# LZ3003_3.net
KiCad netlist of a schematic drawn in EAGLE
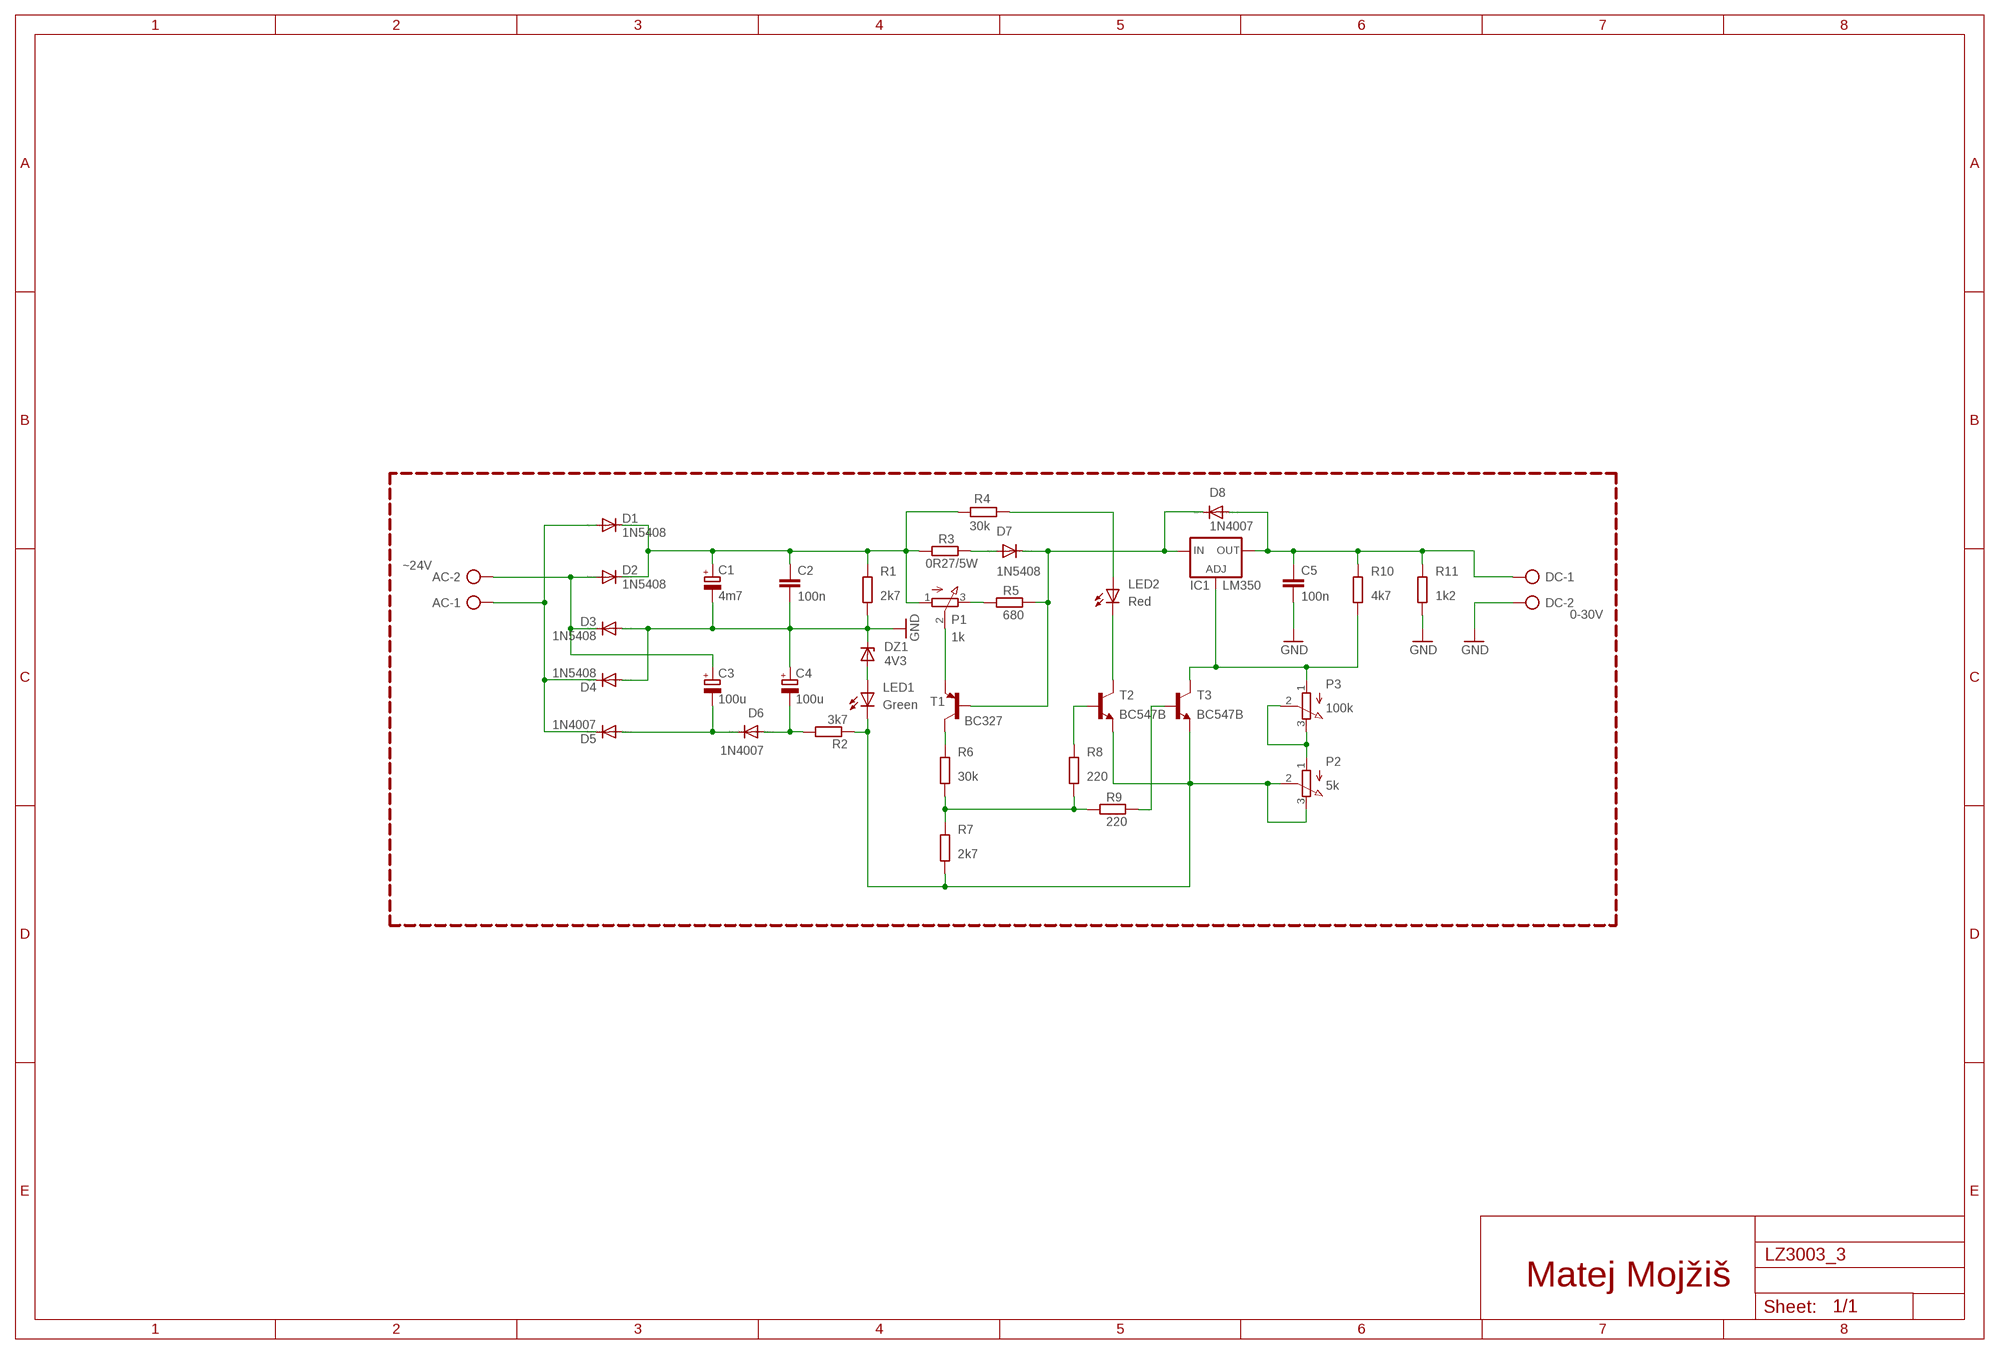
[diagram p0: schematic, sheet 1]

(export (version "E")
  (design (tool "Eeschema 10.0.6"))
  (components
    (comp (ref "AC")
      (value "~24V")
      (footprint "eagle-import:W237-102")
      (fields (field (name "MPN") "237-102"))
      (libsource (lib "eagle-import") (part "W237-102"))
    )
    (comp (ref "C1")
      (value "4m7")
      (footprint "eagle-import:E7,5-16")
      (libsource (lib "eagle-import") (part "CPOL-EUE7.5-16"))
    )
    (comp (ref "C2")
      (value "100n")
      (footprint "eagle-import:C050-025X075")
      (libsource (lib "eagle-import") (part "C-EU050-025X075"))
    )
    (comp (ref "C3")
      (value "100u")
      (footprint "eagle-import:E5-8,5")
      (libsource (lib "eagle-import") (part "CPOL-EUE5-8.5"))
    )
    (comp (ref "C4")
      (value "100u")
      (footprint "eagle-import:E5-8,5")
      (libsource (lib "eagle-import") (part "CPOL-EUE5-8.5"))
    )
    (comp (ref "C5")
      (value "100n")
      (footprint "eagle-import:C050-025X075")
      (libsource (lib "eagle-import") (part "C-EU050-025X075"))
    )
    (comp (ref "D1")
      (value "1N5408")
      (footprint "eagle-import:DO201-15")
      (libsource (lib "eagle-import") (part "1N5400"))
    )
    (comp (ref "D2")
      (value "1N5408")
      (footprint "eagle-import:DO201-15")
      (libsource (lib "eagle-import") (part "1N5400"))
    )
    (comp (ref "D3")
      (value "1N5408")
      (footprint "eagle-import:DO201-15")
      (libsource (lib "eagle-import") (part "1N5400"))
    )
    (comp (ref "D4")
      (value "1N5408")
      (footprint "eagle-import:DO201-15")
      (libsource (lib "eagle-import") (part "1N5400"))
    )
    (comp (ref "D5")
      (value "1N4007")
      (footprint "eagle-import:DO41-10")
      (libsource (lib "eagle-import") (part "1N4004"))
    )
    (comp (ref "D6")
      (value "1N4007")
      (footprint "eagle-import:DO41-10")
      (libsource (lib "eagle-import") (part "1N4004"))
    )
    (comp (ref "D7")
      (value "1N5408")
      (footprint "eagle-import:DO201-15")
      (libsource (lib "eagle-import") (part "1N5400"))
    )
    (comp (ref "D8")
      (value "1N4007")
      (footprint "eagle-import:DO41-10")
      (libsource (lib "eagle-import") (part "1N4004"))
    )
    (comp (ref "DC")
      (value "0-30V")
      (footprint "eagle-import:W237-102")
      (fields (field (name "MPN") "237-102"))
      (libsource (lib "eagle-import") (part "W237-102"))
    )
    (comp (ref "DZ1")
      (value "4V3")
      (footprint "eagle-import:DO34Z7")
      (libsource (lib "eagle-import") (part "ZENER-DIODEDO34-7"))
    )
    (comp (ref "IC1")
      (value "LM350")
      (footprint "eagle-import:317TS")
      (libsource (lib "eagle-import") (part "LM317TS"))
    )
    (comp (ref "LED1")
      (value "Green")
      (footprint "eagle-import:LED5MM")
      (libsource (lib "eagle-import") (part "LED5MM"))
    )
    (comp (ref "LED2")
      (value "Red")
      (footprint "eagle-import:LED5MM")
      (libsource (lib "eagle-import") (part "LED5MM"))
    )
    (comp (ref "P1")
      (value "1k")
      (footprint "eagle-import:3RP_1610N")
      (libsource (lib "eagle-import") (part "3RP/1610N"))
    )
    (comp (ref "P2")
      (value "5k")
      (footprint "eagle-import:3RP_1610N")
      (libsource (lib "eagle-import") (part "3RP/1610N"))
    )
    (comp (ref "P3")
      (value "100k")
      (footprint "eagle-import:3RP_1610N")
      (libsource (lib "eagle-import") (part "3RP/1610N"))
    )
    (comp (ref "R1")
      (value "2k7")
      (footprint "eagle-import:0207_7")
      (libsource (lib "eagle-import") (part "R-EU_0207/7"))
    )
    (comp (ref "R2")
      (value "3k7")
      (footprint "eagle-import:0207_7")
      (libsource (lib "eagle-import") (part "R-EU_0207/7"))
    )
    (comp (ref "R3")
      (value "0R27/5W")
      (footprint "eagle-import:0617_22")
      (libsource (lib "eagle-import") (part "R-EU_0617/22"))
    )
    (comp (ref "R4")
      (value "30k")
      (footprint "eagle-import:0207_7")
      (libsource (lib "eagle-import") (part "R-EU_0207/7"))
    )
    (comp (ref "R5")
      (value "680")
      (footprint "eagle-import:0207_7")
      (libsource (lib "eagle-import") (part "R-EU_0207/7"))
    )
    (comp (ref "R6")
      (value "30k")
      (footprint "eagle-import:0207_7")
      (libsource (lib "eagle-import") (part "R-EU_0207/7"))
    )
    (comp (ref "R7")
      (value "2k7")
      (footprint "eagle-import:0207_7")
      (libsource (lib "eagle-import") (part "R-EU_0207/7"))
    )
    (comp (ref "R8")
      (value "220")
      (footprint "eagle-import:0207_7")
      (libsource (lib "eagle-import") (part "R-EU_0207/7"))
    )
    (comp (ref "R9")
      (value "220")
      (footprint "eagle-import:0207_7")
      (libsource (lib "eagle-import") (part "R-EU_0207/7"))
    )
    (comp (ref "R10")
      (value "4k7")
      (footprint "eagle-import:0207_7")
      (libsource (lib "eagle-import") (part "R-EU_0207/7"))
    )
    (comp (ref "R11")
      (value "1k2")
      (footprint "eagle-import:0207_7")
      (libsource (lib "eagle-import") (part "R-EU_0207/7"))
    )
    (comp (ref "T1")
      (value "BC327")
      (footprint "eagle-import:TO92-EBC")
      (libsource (lib "eagle-import") (part "BC327"))
    )
    (comp (ref "T2")
      (value "BC547B")
      (footprint "eagle-import:TO92-CBE")
      (libsource (lib "eagle-import") (part "-NPN-TO92-CBEBC547B"))
    )
    (comp (ref "T3")
      (value "BC547B")
      (footprint "eagle-import:TO92-CBE")
      (libsource (lib "eagle-import") (part "-NPN-TO92-CBEBC547B"))
    )
  )
  (nets
    (net (code "1") (name "GND") (class "Default")
      (node (ref "C1") (pin "-") (pinfunction "-_-") (pintype "passive"))
      (node (ref "C2") (pin "2") (pinfunction "2_2") (pintype "passive"))
      (node (ref "C4") (pin "+") (pinfunction "+_+") (pintype "passive"))
      (node (ref "C5") (pin "2") (pinfunction "2_2") (pintype "passive"))
      (node (ref "D3") (pin "A") (pinfunction "A_A") (pintype "passive"))
      (node (ref "D4") (pin "A") (pinfunction "A_A") (pintype "passive"))
      (node (ref "DC") (pin "2") (pinfunction "KL_2") (pintype "passive"))
      (node (ref "DZ1") (pin "C") (pinfunction "C_C") (pintype "passive"))
      (node (ref "R1") (pin "2") (pinfunction "2_2") (pintype "passive"))
      (node (ref "R11") (pin "1") (pinfunction "1_1") (pintype "passive"))
    )
    (net (code "2") (name "Net-(ACA-KL)") (class "Default")
      (node (ref "AC") (pin "1") (pinfunction "KL_1") (pintype "passive"))
      (node (ref "D1") (pin "A") (pinfunction "A_A") (pintype "passive"))
      (node (ref "D4") (pin "C") (pinfunction "C_C") (pintype "passive"))
      (node (ref "D5") (pin "C") (pinfunction "C_C") (pintype "passive"))
    )
    (net (code "3") (name "Net-(ACB-KL)") (class "Default")
      (node (ref "AC") (pin "2") (pinfunction "KL_2") (pintype "passive"))
      (node (ref "C3") (pin "+") (pinfunction "+_+") (pintype "passive"))
      (node (ref "D2") (pin "A") (pinfunction "A_A") (pintype "passive"))
      (node (ref "D3") (pin "C") (pinfunction "C_C") (pintype "passive"))
    )
    (net (code "4") (name "Net-(C3-Pad-)") (class "Default")
      (node (ref "C3") (pin "-") (pinfunction "-_-") (pintype "passive"))
      (node (ref "D5") (pin "A") (pinfunction "A_A") (pintype "passive"))
      (node (ref "D6") (pin "C") (pinfunction "C_C") (pintype "passive"))
    )
    (net (code "5") (name "Net-(C4-Pad-)") (class "Default")
      (node (ref "C4") (pin "-") (pinfunction "-_-") (pintype "passive"))
      (node (ref "D6") (pin "A") (pinfunction "A_A") (pintype "passive"))
      (node (ref "R2") (pin "2") (pinfunction "2_2") (pintype "passive"))
    )
    (net (code "6") (name "Net-(D7-PadA)") (class "Default")
      (node (ref "D7") (pin "A") (pinfunction "A_A") (pintype "passive"))
      (node (ref "R3") (pin "2") (pinfunction "2_2") (pintype "passive"))
    )
    (net (code "7") (name "Net-(DCA-KL)") (class "Default")
      (node (ref "C5") (pin "1") (pinfunction "1_1") (pintype "passive"))
      (node (ref "D8") (pin "A") (pinfunction "A_A") (pintype "passive"))
      (node (ref "DC") (pin "1") (pinfunction "KL_1") (pintype "passive"))
      (node (ref "IC1") (pin "2") (pinfunction "OUT_2") (pintype "passive"))
      (node (ref "R10") (pin "2") (pinfunction "2_2") (pintype "passive"))
      (node (ref "R11") (pin "2") (pinfunction "2_2") (pintype "passive"))
    )
    (net (code "8") (name "Net-(DZ1-PadA)") (class "Default")
      (node (ref "DZ1") (pin "A") (pinfunction "A_A") (pintype "passive"))
      (node (ref "LED1") (pin "A") (pinfunction "A_A") (pintype "passive"))
    )
    (net (code "9") (name "Net-(IC1-ADJ)") (class "Default")
      (node (ref "IC1") (pin "1") (pinfunction "ADJ_1") (pintype "input"))
      (node (ref "P3") (pin "1") (pinfunction "A_1") (pintype "passive"))
      (node (ref "R10") (pin "1") (pinfunction "1_1") (pintype "passive"))
      (node (ref "T3") (pin "C") (pinfunction "C_C") (pintype "passive"))
    )
    (net (code "10") (name "Net-(IC1-IN)") (class "Default")
      (node (ref "D7") (pin "C") (pinfunction "C_C") (pintype "passive"))
      (node (ref "D8") (pin "C") (pinfunction "C_C") (pintype "passive"))
      (node (ref "IC1") (pin "3") (pinfunction "IN_3") (pintype "input"))
      (node (ref "R5") (pin "2") (pinfunction "2_2") (pintype "passive"))
      (node (ref "T1") (pin "B") (pinfunction "B_B") (pintype "passive"))
    )
    (net (code "11") (name "Net-(LED1-C)") (class "Default")
      (node (ref "LED1") (pin "K") (pinfunction "C_K") (pintype "passive"))
      (node (ref "P2") (pin "2") (pinfunction "S_2") (pintype "passive"))
      (node (ref "P2") (pin "3") (pinfunction "E_3") (pintype "passive"))
      (node (ref "R2") (pin "1") (pinfunction "1_1") (pintype "passive"))
      (node (ref "R7") (pin "1") (pinfunction "1_1") (pintype "passive"))
      (node (ref "T2") (pin "E") (pinfunction "E_E") (pintype "passive"))
      (node (ref "T3") (pin "E") (pinfunction "E_E") (pintype "passive"))
    )
    (net (code "12") (name "Net-(LED2-C)") (class "Default")
      (node (ref "LED2") (pin "K") (pinfunction "C_K") (pintype "passive"))
      (node (ref "T2") (pin "C") (pinfunction "C_C") (pintype "passive"))
    )
    (net (code "13") (name "Net-(LED2-PadA)") (class "Default")
      (node (ref "LED2") (pin "A") (pinfunction "A_A") (pintype "passive"))
      (node (ref "R4") (pin "1") (pinfunction "1_1") (pintype "passive"))
    )
    (net (code "14") (name "Net-(P1-A)") (class "Default")
      (node (ref "C1") (pin "+") (pinfunction "+_+") (pintype "passive"))
      (node (ref "C2") (pin "1") (pinfunction "1_1") (pintype "passive"))
      (node (ref "D1") (pin "C") (pinfunction "C_C") (pintype "passive"))
      (node (ref "D2") (pin "C") (pinfunction "C_C") (pintype "passive"))
      (node (ref "P1") (pin "1") (pinfunction "A_1") (pintype "passive"))
      (node (ref "R1") (pin "1") (pinfunction "1_1") (pintype "passive"))
      (node (ref "R3") (pin "1") (pinfunction "1_1") (pintype "passive"))
      (node (ref "R4") (pin "2") (pinfunction "2_2") (pintype "passive"))
    )
    (net (code "15") (name "Net-(P1-E)") (class "Default")
      (node (ref "P1") (pin "3") (pinfunction "E_3") (pintype "passive"))
      (node (ref "R5") (pin "1") (pinfunction "1_1") (pintype "passive"))
    )
    (net (code "16") (name "Net-(P1-S)") (class "Default")
      (node (ref "P1") (pin "2") (pinfunction "S_2") (pintype "passive"))
      (node (ref "T1") (pin "E") (pinfunction "E_E") (pintype "passive"))
    )
    (net (code "17") (name "Net-(P2-A)") (class "Default")
      (node (ref "P2") (pin "1") (pinfunction "A_1") (pintype "passive"))
      (node (ref "P3") (pin "2") (pinfunction "S_2") (pintype "passive"))
      (node (ref "P3") (pin "3") (pinfunction "E_3") (pintype "passive"))
    )
    (net (code "18") (name "Net-(R6-Pad1)") (class "Default")
      (node (ref "R6") (pin "1") (pinfunction "1_1") (pintype "passive"))
      (node (ref "R7") (pin "2") (pinfunction "2_2") (pintype "passive"))
      (node (ref "R8") (pin "1") (pinfunction "1_1") (pintype "passive"))
      (node (ref "R9") (pin "1") (pinfunction "1_1") (pintype "passive"))
    )
    (net (code "19") (name "Net-(R6-Pad2)") (class "Default")
      (node (ref "R6") (pin "2") (pinfunction "2_2") (pintype "passive"))
      (node (ref "T1") (pin "C") (pinfunction "C_C") (pintype "passive"))
    )
    (net (code "20") (name "Net-(R8-Pad2)") (class "Default")
      (node (ref "R8") (pin "2") (pinfunction "2_2") (pintype "passive"))
      (node (ref "T2") (pin "B") (pinfunction "B_B") (pintype "passive"))
    )
    (net (code "21") (name "Net-(R9-Pad2)") (class "Default")
      (node (ref "R9") (pin "2") (pinfunction "2_2") (pintype "passive"))
      (node (ref "T3") (pin "B") (pinfunction "B_B") (pintype "passive"))
    )
  )
)
